# DIB_Driver_Interface.net
KiCad netlist of a schematic drawn in Altium Designer
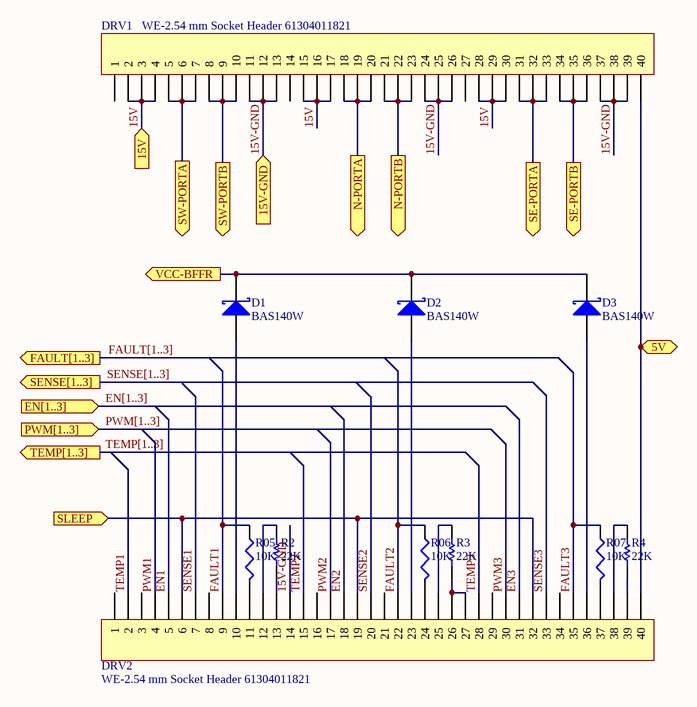
[diagram p0: DIB_Driver_Interface.SchDoc]

(export (version "E")
  (design (tool "Eeschema 10.0.6"))
  (components
    (comp (ref "D1")
      (value "BAS140W")
      (footprint "SOD-323")
      (description "Silicon AF Schottky Diode for High-Speed Switching")
      (fields (field (name "PUBLISHER") "Altium Limited"))
      (libsource (lib "Infineon Discrete Diode") (part "BAS140W"))
    )
    (comp (ref "D2")
      (value "BAS140W")
      (footprint "SOD-323")
      (description "Silicon AF Schottky Diode for High-Speed Switching")
      (fields (field (name "PUBLISHER") "Altium Limited"))
      (libsource (lib "Infineon Discrete Diode") (part "BAS140W"))
    )
    (comp (ref "D3")
      (value "BAS140W")
      (footprint "SOD-323")
      (description "Silicon AF Schottky Diode for High-Speed Switching")
      (fields (field (name "PUBLISHER") "Altium Limited"))
      (libsource (lib "Infineon Discrete Diode") (part "BAS140W"))
    )
    (comp (ref "DRV1")
      (value "WE-2.54 mm Socket Header 61304011821")
      (footprint "61304011821")
      (description "WR-PHD 2.54 mm Socket Header")
      (fields
        (field (name "MANUFACTURER") "Würth Elektronik eiSos GmbH")
        (field (name "PARTNO") "61304011821")
        (field (name "CREATED BY") "Karrer Zheng")
      )
      (libsource (lib "WE_WR-PHD_Socket Header_2.54mm_rev15c") (part "WE-2.54 mm Socket Header 61304011821"))
    )
    (comp (ref "DRV2")
      (value "WE-2.54 mm Socket Header 61304011821")
      (footprint "61304011821")
      (description "WR-PHD 2.54 mm Socket Header")
      (fields
        (field (name "MANUFACTURER") "Würth Elektronik eiSos GmbH")
        (field (name "PARTNO") "61304011821")
        (field (name "CREATED BY") "Karrer Zheng")
      )
      (libsource (lib "") (part "WE-2.54 mm Socket Header 61304011821_1"))
    )
    (comp (ref "R2")
      (value "22K")
      (footprint "AXIAL-0.3")
      (description "Resistor")
      (fields (field (name "PUBLISHER") "Altium Limited"))
      (libsource (lib "Miscellaneous Devices") (part "Res1"))
    )
    (comp (ref "R3")
      (value "22K")
      (footprint "AXIAL-0.3")
      (description "Resistor")
      (fields (field (name "PUBLISHER") "Altium Limited"))
      (libsource (lib "Miscellaneous Devices") (part "Res1"))
    )
    (comp (ref "R4")
      (value "22K")
      (footprint "AXIAL-0.3")
      (description "Resistor")
      (fields (field (name "PUBLISHER") "Altium Limited"))
      (libsource (lib "Miscellaneous Devices") (part "Res1"))
    )
    (comp (ref "R05")
      (value "10K")
      (footprint "J1-0603")
      (description "Resistor")
      (fields (field (name "PUBLISHER") "Altium Limited"))
      (libsource (lib "Miscellaneous Devices") (part "Res3"))
    )
    (comp (ref "R06")
      (value "10K")
      (footprint "J1-0603")
      (description "Resistor")
      (fields (field (name "PUBLISHER") "Altium Limited"))
      (libsource (lib "Miscellaneous Devices") (part "Res3"))
    )
    (comp (ref "R07")
      (value "10K")
      (footprint "J1-0603")
      (description "Resistor")
      (fields (field (name "PUBLISHER") "Altium Limited"))
      (libsource (lib "Miscellaneous Devices") (part "Res3"))
    )
  )
  (nets
    (net (code "1") (name "/5V") (class "Default")
      (node (ref "DRV1") (pin "40") (pinfunction "40_40") (pintype "passive"))
      (node (ref "DRV2") (pin "40") (pinfunction "40_40") (pintype "passive"))
    )
    (net (code "2") (name "/15V") (class "Default")
      (node (ref "DRV1") (pin "15") (pinfunction "15_15") (pintype "passive"))
      (node (ref "DRV1") (pin "16") (pinfunction "16_16") (pintype "passive"))
      (node (ref "DRV1") (pin "17") (pinfunction "17_17") (pintype "passive"))
      (node (ref "DRV1") (pin "2") (pinfunction "2_2") (pintype "passive"))
      (node (ref "DRV1") (pin "28") (pinfunction "28_28") (pintype "passive"))
      (node (ref "DRV1") (pin "29") (pinfunction "29_29") (pintype "passive"))
      (node (ref "DRV1") (pin "3") (pinfunction "3_3") (pintype "passive"))
      (node (ref "DRV1") (pin "30") (pinfunction "30_30") (pintype "passive"))
      (node (ref "DRV1") (pin "4") (pinfunction "4_4") (pintype "passive"))
    )
    (net (code "3") (name "/15V-GND") (class "Default")
      (node (ref "DRV1") (pin "11") (pinfunction "11_11") (pintype "passive"))
      (node (ref "DRV1") (pin "12") (pinfunction "12_12") (pintype "passive"))
      (node (ref "DRV1") (pin "13") (pinfunction "13_13") (pintype "passive"))
      (node (ref "DRV1") (pin "24") (pinfunction "24_24") (pintype "passive"))
      (node (ref "DRV1") (pin "25") (pinfunction "25_25") (pintype "passive"))
      (node (ref "DRV1") (pin "26") (pinfunction "26_26") (pintype "passive"))
      (node (ref "DRV1") (pin "37") (pinfunction "37_37") (pintype "passive"))
      (node (ref "DRV1") (pin "38") (pinfunction "38_38") (pintype "passive"))
      (node (ref "DRV1") (pin "39") (pinfunction "39_39") (pintype "passive"))
      (node (ref "DRV2") (pin "14") (pinfunction "14_14") (pintype "passive"))
    )
    (net (code "4") (name "/EN1") (class "Default")
      (node (ref "DRV2") (pin "5") (pinfunction "5_5") (pintype "passive"))
    )
    (net (code "5") (name "/EN2") (class "Default")
      (node (ref "DRV2") (pin "18") (pinfunction "18_18") (pintype "passive"))
    )
    (net (code "6") (name "/EN3") (class "Default")
      (node (ref "DRV2") (pin "31") (pinfunction "31_31") (pintype "passive"))
    )
    (net (code "8") (name "/FAULT1") (class "Default")
      (node (ref "DRV2") (pin "9") (pinfunction "9_9") (pintype "passive"))
      (node (ref "R05") (pin "1") (pinfunction "1_1") (pintype "passive"))
    )
    (net (code "9") (name "/FAULT2") (class "Default")
      (node (ref "DRV2") (pin "22") (pinfunction "22_22") (pintype "passive"))
      (node (ref "R06") (pin "1") (pinfunction "1_1") (pintype "passive"))
    )
    (net (code "10") (name "/FAULT3") (class "Default")
      (node (ref "DRV2") (pin "35") (pinfunction "35_35") (pintype "passive"))
      (node (ref "R07") (pin "1") (pinfunction "1_1") (pintype "passive"))
    )
    (net (code "12") (name "/N-PORTA") (class "Default")
      (node (ref "DRV1") (pin "18") (pinfunction "18_18") (pintype "passive"))
      (node (ref "DRV1") (pin "19") (pinfunction "19_19") (pintype "passive"))
      (node (ref "DRV1") (pin "20") (pinfunction "20_20") (pintype "passive"))
    )
    (net (code "13") (name "/N-PORTB") (class "Default")
      (node (ref "DRV1") (pin "21") (pinfunction "21_21") (pintype "passive"))
      (node (ref "DRV1") (pin "22") (pinfunction "22_22") (pintype "passive"))
      (node (ref "DRV1") (pin "23") (pinfunction "23_23") (pintype "passive"))
    )
    (net (code "14") (name "/PWM1") (class "Default")
      (node (ref "DRV2") (pin "4") (pinfunction "4_4") (pintype "passive"))
    )
    (net (code "15") (name "/PWM2") (class "Default")
      (node (ref "DRV2") (pin "17") (pinfunction "17_17") (pintype "passive"))
    )
    (net (code "16") (name "/PWM3") (class "Default")
      (node (ref "DRV2") (pin "30") (pinfunction "30_30") (pintype "passive"))
    )
    (net (code "18") (name "/SE-PORTA") (class "Default")
      (node (ref "DRV1") (pin "31") (pinfunction "31_31") (pintype "passive"))
      (node (ref "DRV1") (pin "32") (pinfunction "32_32") (pintype "passive"))
      (node (ref "DRV1") (pin "33") (pinfunction "33_33") (pintype "passive"))
    )
    (net (code "19") (name "/SE-PORTB") (class "Default")
      (node (ref "DRV1") (pin "34") (pinfunction "34_34") (pintype "passive"))
      (node (ref "DRV1") (pin "35") (pinfunction "35_35") (pintype "passive"))
      (node (ref "DRV1") (pin "36") (pinfunction "36_36") (pintype "passive"))
    )
    (net (code "20") (name "/SENSE1") (class "Default")
      (node (ref "DRV2") (pin "7") (pinfunction "7_7") (pintype "passive"))
    )
    (net (code "21") (name "/SENSE2") (class "Default")
      (node (ref "DRV2") (pin "20") (pinfunction "20_20") (pintype "passive"))
    )
    (net (code "22") (name "/SENSE3") (class "Default")
      (node (ref "DRV2") (pin "33") (pinfunction "33_33") (pintype "passive"))
    )
    (net (code "24") (name "/SLEEP") (class "Default")
      (node (ref "DRV2") (pin "19") (pinfunction "19_19") (pintype "passive"))
      (node (ref "DRV2") (pin "32") (pinfunction "32_32") (pintype "passive"))
      (node (ref "DRV2") (pin "6") (pinfunction "6_6") (pintype "passive"))
    )
    (net (code "25") (name "/SW-PORTA") (class "Default")
      (node (ref "DRV1") (pin "5") (pinfunction "5_5") (pintype "passive"))
      (node (ref "DRV1") (pin "6") (pinfunction "6_6") (pintype "passive"))
      (node (ref "DRV1") (pin "7") (pinfunction "7_7") (pintype "passive"))
    )
    (net (code "26") (name "/SW-PORTB") (class "Default")
      (node (ref "DRV1") (pin "10") (pinfunction "10_10") (pintype "passive"))
      (node (ref "DRV1") (pin "8") (pinfunction "8_8") (pintype "passive"))
      (node (ref "DRV1") (pin "9") (pinfunction "9_9") (pintype "passive"))
    )
    (net (code "27") (name "/TEMP1") (class "Default")
      (node (ref "DRV2") (pin "2") (pinfunction "2_2") (pintype "passive"))
    )
    (net (code "28") (name "/TEMP2") (class "Default")
      (node (ref "DRV2") (pin "15") (pinfunction "15_15") (pintype "passive"))
    )
    (net (code "29") (name "/TEMP3") (class "Default")
      (node (ref "DRV2") (pin "28") (pinfunction "28_28") (pintype "passive"))
    )
    (net (code "31") (name "/VCC-BFFR") (class "Default")
      (node (ref "D1") (pin "1") (pinfunction "K_1") (pintype "passive"))
      (node (ref "D2") (pin "1") (pinfunction "K_1") (pintype "passive"))
      (node (ref "D3") (pin "1") (pinfunction "K_1") (pintype "passive"))
    )
    (net (code "32") (name "Net-(D1-A)") (class "Default")
      (node (ref "D1") (pin "2") (pinfunction "A_2") (pintype "passive"))
      (node (ref "DRV2") (pin "10") (pinfunction "10_10") (pintype "passive"))
    )
    (net (code "33") (name "Net-(D2-A)") (class "Default")
      (node (ref "D2") (pin "2") (pinfunction "A_2") (pintype "passive"))
      (node (ref "DRV2") (pin "23") (pinfunction "23_23") (pintype "passive"))
    )
    (net (code "34") (name "Net-(D3-A)") (class "Default")
      (node (ref "D3") (pin "2") (pinfunction "A_2") (pintype "passive"))
      (node (ref "DRV2") (pin "36") (pinfunction "36_36") (pintype "passive"))
    )
    (net (code "35") (name "Net-(DRV2-Pad11)") (class "Default")
      (node (ref "DRV2") (pin "11") (pinfunction "11_11") (pintype "passive"))
      (node (ref "R05") (pin "2") (pinfunction "2_2") (pintype "passive"))
    )
    (net (code "36") (name "Net-(DRV2-Pad12)") (class "Default")
      (node (ref "DRV2") (pin "12") (pinfunction "12_12") (pintype "passive"))
      (node (ref "R2") (pin "2") (pinfunction "2_2") (pintype "passive"))
    )
    (net (code "37") (name "Net-(DRV2-Pad13)") (class "Default")
      (node (ref "DRV2") (pin "13") (pinfunction "13_13") (pintype "passive"))
      (node (ref "R2") (pin "1") (pinfunction "1_1") (pintype "passive"))
    )
    (net (code "38") (name "Net-(DRV2-Pad24)") (class "Default")
      (node (ref "DRV2") (pin "24") (pinfunction "24_24") (pintype "passive"))
      (node (ref "R06") (pin "2") (pinfunction "2_2") (pintype "passive"))
    )
    (net (code "39") (name "Net-(DRV2-Pad25)") (class "Default")
      (node (ref "DRV2") (pin "25") (pinfunction "25_25") (pintype "passive"))
      (node (ref "R3") (pin "2") (pinfunction "2_2") (pintype "passive"))
    )
    (net (code "40") (name "Net-(DRV2-Pad26)") (class "Default")
      (node (ref "DRV2") (pin "26") (pinfunction "26_26") (pintype "passive"))
      (node (ref "DRV2") (pin "27") (pinfunction "27_27") (pintype "passive"))
      (node (ref "R3") (pin "1") (pinfunction "1_1") (pintype "passive"))
    )
    (net (code "41") (name "Net-(DRV2-Pad37)") (class "Default")
      (node (ref "DRV2") (pin "37") (pinfunction "37_37") (pintype "passive"))
      (node (ref "R07") (pin "2") (pinfunction "2_2") (pintype "passive"))
    )
    (net (code "42") (name "Net-(DRV2-Pad38)") (class "Default")
      (node (ref "DRV2") (pin "38") (pinfunction "38_38") (pintype "passive"))
      (node (ref "R4") (pin "2") (pinfunction "2_2") (pintype "passive"))
    )
    (net (code "43") (name "Net-(DRV2-Pad39)") (class "Default")
      (node (ref "DRV2") (pin "39") (pinfunction "39_39") (pintype "passive"))
      (node (ref "R4") (pin "1") (pinfunction "1_1") (pintype "passive"))
    )
    (net (code "44") (name "unconnected-(DRV1-Pad1)") (class "Default")
      (node (ref "DRV1") (pin "1") (pinfunction "1_1") (pintype "passive"))
    )
    (net (code "45") (name "unconnected-(DRV1-Pad14)") (class "Default")
      (node (ref "DRV1") (pin "14") (pinfunction "14_14") (pintype "passive"))
    )
    (net (code "46") (name "unconnected-(DRV1-Pad27)") (class "Default")
      (node (ref "DRV1") (pin "27") (pinfunction "27_27") (pintype "passive"))
    )
    (net (code "47") (name "unconnected-(DRV2-Pad1)") (class "Default")
      (node (ref "DRV2") (pin "1") (pinfunction "1_1") (pintype "passive"))
    )
    (net (code "48") (name "unconnected-(DRV2-Pad3)") (class "Default")
      (node (ref "DRV2") (pin "3") (pinfunction "3_3") (pintype "passive"))
    )
    (net (code "49") (name "unconnected-(DRV2-Pad8)") (class "Default")
      (node (ref "DRV2") (pin "8") (pinfunction "8_8") (pintype "passive"))
    )
    (net (code "50") (name "unconnected-(DRV2-Pad16)") (class "Default")
      (node (ref "DRV2") (pin "16") (pinfunction "16_16") (pintype "passive"))
    )
    (net (code "51") (name "unconnected-(DRV2-Pad21)") (class "Default")
      (node (ref "DRV2") (pin "21") (pinfunction "21_21") (pintype "passive"))
    )
    (net (code "52") (name "unconnected-(DRV2-Pad29)") (class "Default")
      (node (ref "DRV2") (pin "29") (pinfunction "29_29") (pintype "passive"))
    )
    (net (code "53") (name "unconnected-(DRV2-Pad34)") (class "Default")
      (node (ref "DRV2") (pin "34") (pinfunction "34_34") (pintype "passive"))
    )
  )
)
